# Sheet_X_buzzer.net
KiCad netlist of a schematic drawn in Altium Designer
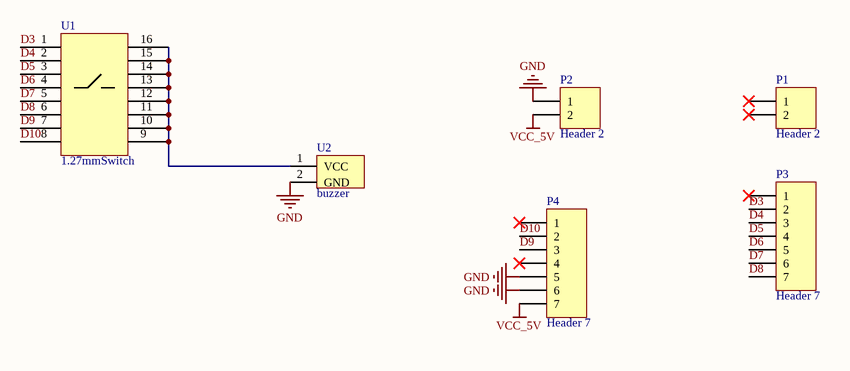
[diagram p0: Sheet_X_buzzer.SchDoc]

(export (version "E")
  (design (tool "Eeschema 10.0.6"))
  (components
    (comp (ref "P1")
      (value "Header 2")
      (footprint "HDR1X2")
      (description "Header, 2-Pin")
      (fields (field (name "PUBLISHER") "Altium Limited"))
      (libsource (lib "Miscellaneous Connectors") (part "Header 2"))
    )
    (comp (ref "P2")
      (value "Header 2")
      (footprint "HDR1X2")
      (description "Header, 2-Pin")
      (fields (field (name "PUBLISHER") "Altium Limited"))
      (libsource (lib "Miscellaneous Connectors") (part "Header 2"))
    )
    (comp (ref "P3")
      (value "Header 7")
      (footprint "HDR1X7")
      (description "Header, 7-Pin")
      (fields (field (name "PUBLISHER") "Altium Limited"))
      (libsource (lib "Miscellaneous Connectors") (part "Header 7"))
    )
    (comp (ref "P4")
      (value "Header 7")
      (footprint "HDR1X7")
      (description "Header, 7-Pin")
      (fields (field (name "PUBLISHER") "Altium Limited"))
      (libsource (lib "Miscellaneous Connectors") (part "Header 7"))
    )
    (comp (ref "U1")
      (value "1.27mmSwitch")
      (footprint "NumberSwitch")
      (description "拨码开关")
      (libsource (lib "Schlib_OLEDMCU") (part "NumberSwitch"))
    )
    (comp (ref "U2")
      (value "buzzer")
      (footprint "buzzer")
      (description "3V蜂鸣器")
      (libsource (lib "Schlib_OLEDMCU") (part "buzzer"))
    )
  )
  (nets
    (net (code "1") (name "/D3") (class "Default")
      (node (ref "P3") (pin "2") (pinfunction "2_2") (pintype "passive"))
      (node (ref "U1") (pin "1") (pinfunction "1_1") (pintype "passive"))
    )
    (net (code "2") (name "/D4") (class "Default")
      (node (ref "P3") (pin "3") (pinfunction "3_3") (pintype "passive"))
      (node (ref "U1") (pin "2") (pinfunction "2_2") (pintype "passive"))
    )
    (net (code "3") (name "/D5") (class "Default")
      (node (ref "P3") (pin "4") (pinfunction "4_4") (pintype "passive"))
      (node (ref "U1") (pin "3") (pinfunction "3_3") (pintype "passive"))
    )
    (net (code "4") (name "/D6") (class "Default")
      (node (ref "P3") (pin "5") (pinfunction "5_5") (pintype "passive"))
      (node (ref "U1") (pin "4") (pinfunction "4_4") (pintype "passive"))
    )
    (net (code "5") (name "/D7") (class "Default")
      (node (ref "P3") (pin "6") (pinfunction "6_6") (pintype "passive"))
      (node (ref "U1") (pin "5") (pinfunction "5_5") (pintype "passive"))
    )
    (net (code "6") (name "/D8") (class "Default")
      (node (ref "P3") (pin "7") (pinfunction "7_7") (pintype "passive"))
      (node (ref "U1") (pin "6") (pinfunction "6_6") (pintype "passive"))
    )
    (net (code "7") (name "/D9") (class "Default")
      (node (ref "P4") (pin "3") (pinfunction "3_3") (pintype "passive"))
      (node (ref "U1") (pin "7") (pinfunction "7_7") (pintype "passive"))
    )
    (net (code "8") (name "/D10") (class "Default")
      (node (ref "P4") (pin "2") (pinfunction "2_2") (pintype "passive"))
      (node (ref "U1") (pin "8") (pinfunction "8_8") (pintype "passive"))
    )
    (net (code "9") (name "GND") (class "Default")
      (node (ref "P2") (pin "1") (pinfunction "1_1") (pintype "passive"))
      (node (ref "P4") (pin "5") (pinfunction "5_5") (pintype "passive"))
      (node (ref "P4") (pin "6") (pinfunction "6_6") (pintype "passive"))
      (node (ref "U2") (pin "2") (pinfunction "GND_2") (pintype "passive"))
    )
    (net (code "10") (name "Net-(U2-VCC)") (class "Default")
      (node (ref "U1") (pin "10") (pinfunction "10_10") (pintype "passive"))
      (node (ref "U1") (pin "11") (pinfunction "11_11") (pintype "passive"))
      (node (ref "U1") (pin "12") (pinfunction "12_12") (pintype "passive"))
      (node (ref "U1") (pin "13") (pinfunction "13_13") (pintype "passive"))
      (node (ref "U1") (pin "14") (pinfunction "14_14") (pintype "passive"))
      (node (ref "U1") (pin "15") (pinfunction "15_15") (pintype "passive"))
      (node (ref "U1") (pin "16") (pinfunction "16_16") (pintype "passive"))
      (node (ref "U1") (pin "9") (pinfunction "9_9") (pintype "passive"))
      (node (ref "U2") (pin "1") (pinfunction "VCC_1") (pintype "passive"))
    )
    (net (code "11") (name "VCC_5V") (class "Default")
      (node (ref "P2") (pin "2") (pinfunction "2_2") (pintype "passive"))
      (node (ref "P4") (pin "7") (pinfunction "7_7") (pintype "passive"))
    )
    (net (code "12") (name "unconnected-(P1-Pad1)") (class "Default")
      (node (ref "P1") (pin "1") (pinfunction "1_1") (pintype "passive+no_connect"))
    )
    (net (code "13") (name "unconnected-(P1-Pad2)") (class "Default")
      (node (ref "P1") (pin "2") (pinfunction "2_2") (pintype "passive+no_connect"))
    )
    (net (code "14") (name "unconnected-(P3-Pad1)") (class "Default")
      (node (ref "P3") (pin "1") (pinfunction "1_1") (pintype "passive+no_connect"))
    )
    (net (code "15") (name "unconnected-(P4-Pad1)") (class "Default")
      (node (ref "P4") (pin "1") (pinfunction "1_1") (pintype "passive+no_connect"))
    )
    (net (code "16") (name "unconnected-(P4-Pad4)") (class "Default")
      (node (ref "P4") (pin "4") (pinfunction "4_4") (pintype "passive+no_connect"))
    )
  )
)
